# OpenProg-18F2550-2.net
KiCad netlist of a schematic drawn in EAGLE
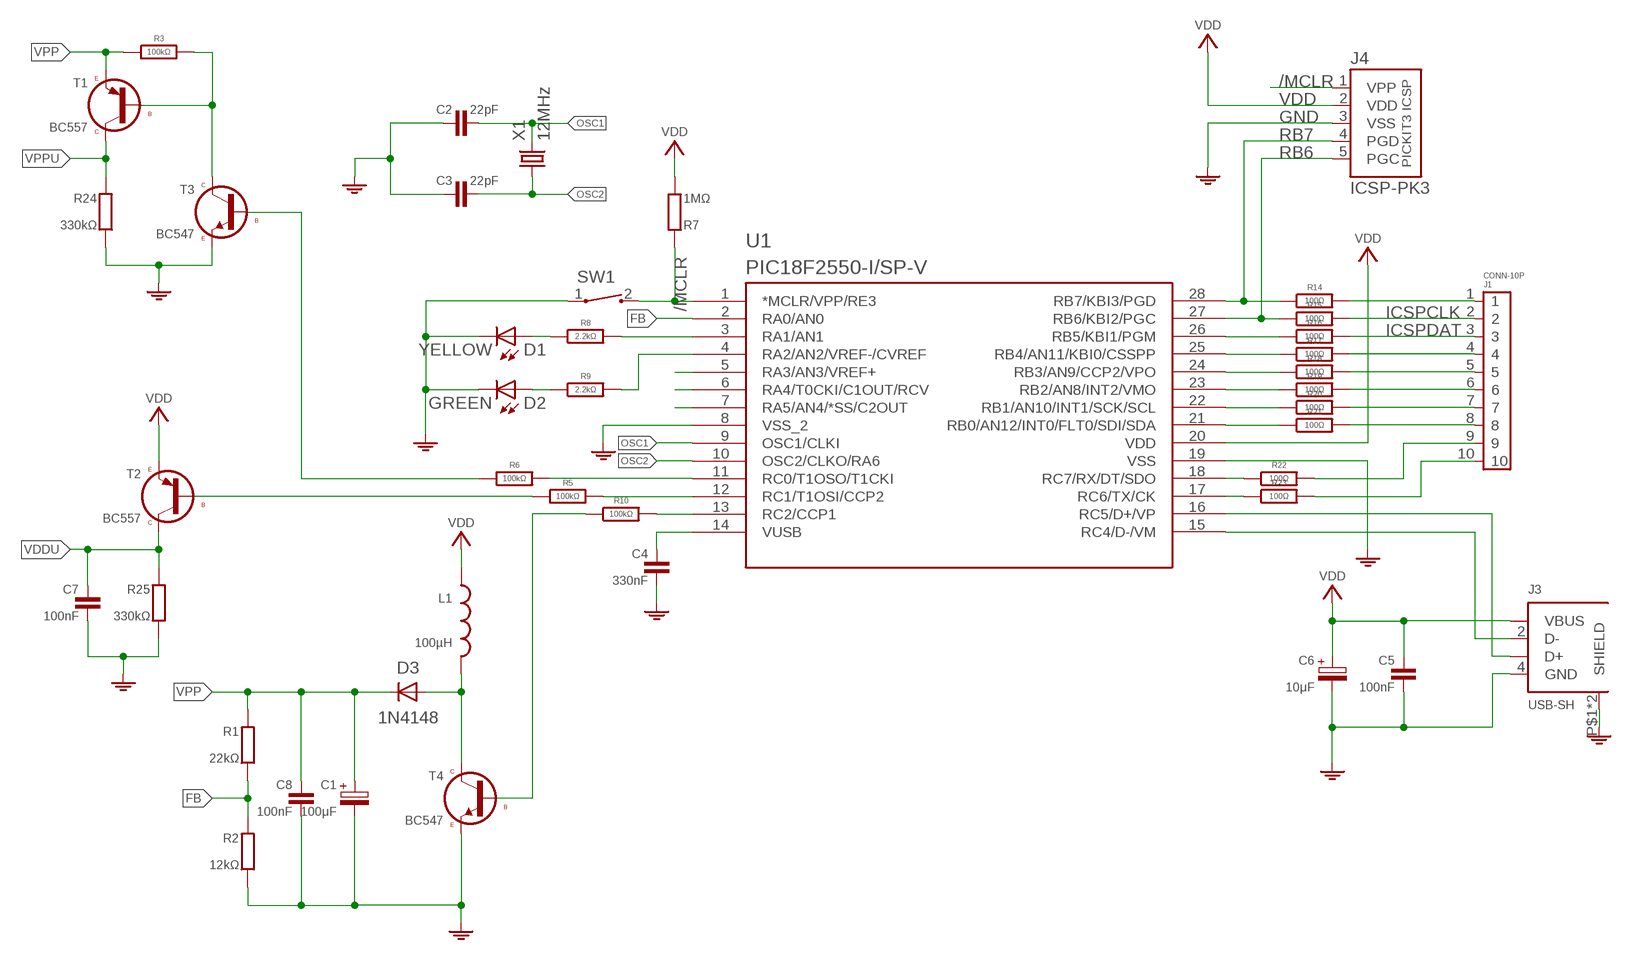
[diagram p0: schematic, sheet 1]

(export (version "E")
  (design (tool "Eeschema 10.0.6"))
  (components
    (comp (ref "C1")
      (value "100μF")
      (footprint "eagle-import:E5-5")
      (libsource (lib "eagle-import") (part "CPOLE5-5"))
    )
    (comp (ref "C2")
      (value "22pF")
      (footprint "eagle-import:C025-015X024")
      (libsource (lib "eagle-import") (part "C-H025-015X024"))
    )
    (comp (ref "C3")
      (value "22pF")
      (footprint "eagle-import:C025-015X024")
      (libsource (lib "eagle-import") (part "C-H025-015X024"))
    )
    (comp (ref "C4")
      (value "330nF")
      (footprint "eagle-import:C050-030X075")
      (libsource (lib "eagle-import") (part "C050-030X075"))
    )
    (comp (ref "C5")
      (value "100nF")
      (footprint "eagle-import:C050-025X075")
      (libsource (lib "eagle-import") (part "C050-025X075"))
    )
    (comp (ref "C6")
      (value "10μF")
      (footprint "eagle-import:E5-5")
      (libsource (lib "eagle-import") (part "CPOLE5-5"))
    )
    (comp (ref "C7")
      (value "100nF")
      (footprint "eagle-import:C050-025X075")
      (libsource (lib "eagle-import") (part "C050-025X075"))
    )
    (comp (ref "C8")
      (value "100nF")
      (footprint "eagle-import:C050-025X075")
      (libsource (lib "eagle-import") (part "C050-025X075"))
    )
    (comp (ref "D1")
      (value "YELLOW")
      (footprint "eagle-import:LED3MM")
      (libsource (lib "eagle-import") (part "LED-H-3MM"))
    )
    (comp (ref "D2")
      (value "GREEN")
      (footprint "eagle-import:LED3MM")
      (libsource (lib "eagle-import") (part "LED-H-3MM"))
    )
    (comp (ref "D3")
      (value "1N4148")
      (footprint "eagle-import:DO34-7")
      (libsource (lib "eagle-import") (part "1N4148-HDO34-7"))
    )
    (comp (ref "J1")
      (value "CONN-10P")
      (footprint "eagle-import:CONN-10P")
      (libsource (lib "eagle-import") (part "CONN-10P"))
    )
    (comp (ref "J3")
      (value "USB-SH")
      (footprint "eagle-import:USB-B-PRINT")
      (libsource (lib "eagle-import") (part "USB-SH"))
    )
    (comp (ref "J4")
      (value "ICSP-PK3")
      (footprint "eagle-import:PIC-PK3")
      (libsource (lib "eagle-import") (part "PICKIT3-ICSP-PK3"))
    )
    (comp (ref "L1")
      (value "100µH")
      (footprint "eagle-import:L-03_10V")
      (libsource (lib "eagle-import") (part "L02/10"))
    )
    (comp (ref "R1")
      (value "22kΩ")
      (footprint "eagle-import:0204_10-V")
      (libsource (lib "eagle-import") (part "R0204/10-V"))
    )
    (comp (ref "R2")
      (value "12kΩ")
      (footprint "eagle-import:0204_10-V")
      (libsource (lib "eagle-import") (part "R0204/10-V"))
    )
    (comp (ref "R3")
      (value "100kΩ")
      (footprint "eagle-import:0204_10-V")
      (libsource (lib "eagle-import") (part "R-H0204/10-V"))
    )
    (comp (ref "R5")
      (value "100kΩ")
      (footprint "eagle-import:0204_10")
      (libsource (lib "eagle-import") (part "R-H0204/10"))
    )
    (comp (ref "R6")
      (value "100kΩ")
      (footprint "eagle-import:0204_10")
      (libsource (lib "eagle-import") (part "R-H0204/10"))
    )
    (comp (ref "R7")
      (value "1MΩ")
      (footprint "eagle-import:0204_10-V")
      (libsource (lib "eagle-import") (part "R0204/10-V"))
    )
    (comp (ref "R8")
      (value "2.2kΩ")
      (footprint "eagle-import:0204_10")
      (libsource (lib "eagle-import") (part "R-H0204/10"))
    )
    (comp (ref "R9")
      (value "2.2kΩ")
      (footprint "eagle-import:0204_10")
      (libsource (lib "eagle-import") (part "R-H0204/10"))
    )
    (comp (ref "R10")
      (value "100kΩ")
      (footprint "eagle-import:0204_10")
      (libsource (lib "eagle-import") (part "R-H0204/10"))
    )
    (comp (ref "R14")
      (value "100Ω")
      (footprint "eagle-import:0204_10")
      (libsource (lib "eagle-import") (part "R-H0204/10"))
    )
    (comp (ref "R15")
      (value "100Ω")
      (footprint "eagle-import:0204_10")
      (libsource (lib "eagle-import") (part "R-H0204/10"))
    )
    (comp (ref "R16")
      (value "100Ω")
      (footprint "eagle-import:0204_10")
      (libsource (lib "eagle-import") (part "R-H0204/10"))
    )
    (comp (ref "R17")
      (value "100Ω")
      (footprint "eagle-import:0204_10")
      (libsource (lib "eagle-import") (part "R-H0204/10"))
    )
    (comp (ref "R18")
      (value "100Ω")
      (footprint "eagle-import:0204_10")
      (libsource (lib "eagle-import") (part "R-H0204/10"))
    )
    (comp (ref "R19")
      (value "100Ω")
      (footprint "eagle-import:0204_10")
      (libsource (lib "eagle-import") (part "R-H0204/10"))
    )
    (comp (ref "R20")
      (value "100Ω")
      (footprint "eagle-import:0204_10")
      (libsource (lib "eagle-import") (part "R-H0204/10"))
    )
    (comp (ref "R21")
      (value "100Ω")
      (footprint "eagle-import:0204_10")
      (libsource (lib "eagle-import") (part "R-H0204/10"))
    )
    (comp (ref "R22")
      (value "100Ω")
      (footprint "eagle-import:0204_10")
      (libsource (lib "eagle-import") (part "R-H0204/10"))
    )
    (comp (ref "R23")
      (value "100Ω")
      (footprint "eagle-import:0204_10")
      (libsource (lib "eagle-import") (part "R-H0204/10"))
    )
    (comp (ref "R24")
      (value "330kΩ")
      (footprint "eagle-import:0204_10-V")
      (libsource (lib "eagle-import") (part "R0204/10-V"))
    )
    (comp (ref "R25")
      (value "330kΩ")
      (footprint "eagle-import:0204_10-V")
      (libsource (lib "eagle-import") (part "R0204/10-V"))
    )
    (comp (ref "SW1")
      (value "PUSHBUTTON-P1T")
      (footprint "eagle-import:PB-1P1T")
      (libsource (lib "eagle-import") (part "PUSHBUTTON-P1T"))
    )
    (comp (ref "T1")
      (value "BC557")
      (footprint "eagle-import:TO92-CBE-A")
      (libsource (lib "eagle-import") (part "BC557CBE-A"))
    )
    (comp (ref "T2")
      (value "BC557")
      (footprint "eagle-import:TO92-CBE-A")
      (libsource (lib "eagle-import") (part "BC557CBE-A"))
    )
    (comp (ref "T3")
      (value "BC547")
      (footprint "eagle-import:TO92-CBE-A")
      (libsource (lib "eagle-import") (part "BC547-A"))
    )
    (comp (ref "T4")
      (value "BC547")
      (footprint "eagle-import:TO92-CBE-A")
      (libsource (lib "eagle-import") (part "BC547-A"))
    )
    (comp (ref "U1")
      (value "PIC18F2550-I/SP-V")
      (footprint "eagle-import:DIL28-3_V")
      (libsource (lib "eagle-import") (part "PIC18F2550-I/SP-V"))
    )
    (comp (ref "X1")
      (value "12MHz")
      (footprint "eagle-import:HC49")
      (libsource (lib "eagle-import") (part "CRYSTALHC49"))
    )
  )
  (nets
    (net (code "1") (name "/ICSPCLK") (class "Default")
      (node (ref "J1") (pin "2") (pinfunction "2_2") (pintype "passive"))
      (node (ref "R15") (pin "2") (pinfunction "2_2") (pintype "passive"))
    )
    (net (code "2") (name "/ICSPDAT") (class "Default")
      (node (ref "J1") (pin "3") (pinfunction "3_3") (pintype "passive"))
      (node (ref "R16") (pin "2") (pinfunction "2_2") (pintype "passive"))
    )
    (net (code "3") (name "/RB6") (class "Default")
      (node (ref "J4") (pin "5") (pinfunction "PGC_5") (pintype "passive"))
      (node (ref "R15") (pin "1") (pinfunction "1_1") (pintype "passive"))
      (node (ref "U1") (pin "27") (pinfunction "RB6/KBI2/PGC_27") (pintype "passive"))
    )
    (net (code "4") (name "/RB7") (class "Default")
      (node (ref "J4") (pin "4") (pinfunction "PGD_4") (pintype "passive"))
      (node (ref "R14") (pin "1") (pinfunction "1_1") (pintype "passive"))
      (node (ref "U1") (pin "28") (pinfunction "RB7/KBI3/PGD_28") (pintype "passive"))
    )
    (net (code "5") (name "/{slash}MCLR") (class "Default")
      (node (ref "J4") (pin "1") (pinfunction "VPP_1") (pintype "passive"))
      (node (ref "R7") (pin "1") (pinfunction "2_1") (pintype "passive"))
      (node (ref "SW1") (pin "2") (pinfunction "2_2") (pintype "passive"))
      (node (ref "U1") (pin "1") (pinfunction "*MCLR/VPP/RE3_1") (pintype "passive"))
    )
    (net (code "6") (name "FB") (class "Default")
      (node (ref "R1") (pin "2") (pinfunction "1_2") (pintype "passive"))
      (node (ref "R2") (pin "1") (pinfunction "2_1") (pintype "passive"))
      (node (ref "U1") (pin "2") (pinfunction "RA0/AN0_2") (pintype "passive"))
    )
    (net (code "7") (name "GND") (class "Default")
      (node (ref "C1") (pin "-") (pinfunction "-_-") (pintype "passive"))
      (node (ref "C2") (pin "1") (pinfunction "1_1") (pintype "passive"))
      (node (ref "C3") (pin "1") (pinfunction "1_1") (pintype "passive"))
      (node (ref "C4") (pin "2") (pinfunction "2_2") (pintype "passive"))
      (node (ref "C5") (pin "2") (pinfunction "2_2") (pintype "passive"))
      (node (ref "C6") (pin "-") (pinfunction "-_-") (pintype "passive"))
      (node (ref "C7") (pin "2") (pinfunction "2_2") (pintype "passive"))
      (node (ref "C8") (pin "2") (pinfunction "2_2") (pintype "passive"))
      (node (ref "D1") (pin "K") (pinfunction "C_K") (pintype "passive"))
      (node (ref "D2") (pin "K") (pinfunction "C_K") (pintype "passive"))
      (node (ref "J3") (pin "4") (pinfunction "GND_4") (pintype "bidirectional"))
      (node (ref "J3") (pin "P$1") (pinfunction "SHIELD_P$1") (pintype "bidirectional"))
      (node (ref "J3") (pin "P$2") (pinfunction "SHIELD_P$2") (pintype "bidirectional"))
      (node (ref "J4") (pin "3") (pinfunction "VSS_3") (pintype "passive"))
      (node (ref "R2") (pin "2") (pinfunction "1_2") (pintype "passive"))
      (node (ref "R24") (pin "2") (pinfunction "1_2") (pintype "passive"))
      (node (ref "R25") (pin "2") (pinfunction "1_2") (pintype "passive"))
      (node (ref "SW1") (pin "1") (pinfunction "1_1") (pintype "passive"))
      (node (ref "T3") (pin "3") (pinfunction "E_3") (pintype "passive"))
      (node (ref "T4") (pin "3") (pinfunction "E_3") (pintype "passive"))
      (node (ref "U1") (pin "19") (pinfunction "VSS_19") (pintype "passive"))
      (node (ref "U1") (pin "8") (pinfunction "VSS_2_8") (pintype "passive"))
    )
    (net (code "8") (name "Net-(D1-PadA)") (class "Default")
      (node (ref "D1") (pin "A") (pinfunction "A_A") (pintype "passive"))
      (node (ref "R8") (pin "1") (pinfunction "1_1") (pintype "passive"))
    )
    (net (code "9") (name "Net-(D2-PadA)") (class "Default")
      (node (ref "D2") (pin "A") (pinfunction "A_A") (pintype "passive"))
      (node (ref "R9") (pin "1") (pinfunction "1_1") (pintype "passive"))
    )
    (net (code "10") (name "Net-(J1-Pad1)") (class "Default")
      (node (ref "J1") (pin "1") (pinfunction "1_1") (pintype "passive"))
      (node (ref "R14") (pin "2") (pinfunction "2_2") (pintype "passive"))
    )
    (net (code "11") (name "Net-(J1-Pad4)") (class "Default")
      (node (ref "J1") (pin "4") (pinfunction "4_4") (pintype "passive"))
      (node (ref "R17") (pin "2") (pinfunction "2_2") (pintype "passive"))
    )
    (net (code "12") (name "Net-(J1-Pad5)") (class "Default")
      (node (ref "J1") (pin "5") (pinfunction "5_5") (pintype "passive"))
      (node (ref "R18") (pin "2") (pinfunction "2_2") (pintype "passive"))
    )
    (net (code "13") (name "Net-(J1-Pad6)") (class "Default")
      (node (ref "J1") (pin "6") (pinfunction "6_6") (pintype "passive"))
      (node (ref "R19") (pin "2") (pinfunction "2_2") (pintype "passive"))
    )
    (net (code "14") (name "Net-(J1-Pad7)") (class "Default")
      (node (ref "J1") (pin "7") (pinfunction "7_7") (pintype "passive"))
      (node (ref "R20") (pin "2") (pinfunction "2_2") (pintype "passive"))
    )
    (net (code "15") (name "Net-(J1-Pad8)") (class "Default")
      (node (ref "J1") (pin "8") (pinfunction "8_8") (pintype "passive"))
      (node (ref "R21") (pin "2") (pinfunction "2_2") (pintype "passive"))
    )
    (net (code "16") (name "Net-(J1-Pad9)") (class "Default")
      (node (ref "J1") (pin "9") (pinfunction "9_9") (pintype "passive"))
      (node (ref "R22") (pin "2") (pinfunction "2_2") (pintype "passive"))
    )
    (net (code "17") (name "Net-(J1-Pad10)") (class "Default")
      (node (ref "J1") (pin "10") (pinfunction "10_10") (pintype "passive"))
      (node (ref "R23") (pin "2") (pinfunction "2_2") (pintype "passive"))
    )
    (net (code "18") (name "Net-(J3-D+)") (class "Default")
      (node (ref "J3") (pin "3") (pinfunction "D+_3") (pintype "bidirectional"))
      (node (ref "U1") (pin "16") (pinfunction "RC5/D+/VP_16") (pintype "passive"))
    )
    (net (code "19") (name "Net-(J3-D-)") (class "Default")
      (node (ref "J3") (pin "2") (pinfunction "D-_2") (pintype "bidirectional"))
      (node (ref "U1") (pin "15") (pinfunction "RC4/D-/VM_15") (pintype "passive"))
    )
    (net (code "20") (name "Net-(T1-B)") (class "Default")
      (node (ref "R3") (pin "2") (pinfunction "2_2") (pintype "passive"))
      (node (ref "T1") (pin "2") (pinfunction "B_2") (pintype "passive"))
      (node (ref "T3") (pin "1") (pinfunction "C_1") (pintype "passive"))
    )
    (net (code "21") (name "Net-(T2-B)") (class "Default")
      (node (ref "R5") (pin "1") (pinfunction "1_1") (pintype "passive"))
      (node (ref "T2") (pin "2") (pinfunction "B_2") (pintype "passive"))
    )
    (net (code "22") (name "Net-(T3-B)") (class "Default")
      (node (ref "R6") (pin "1") (pinfunction "1_1") (pintype "passive"))
      (node (ref "T3") (pin "2") (pinfunction "B_2") (pintype "passive"))
    )
    (net (code "23") (name "Net-(T4-B)") (class "Default")
      (node (ref "R10") (pin "1") (pinfunction "1_1") (pintype "passive"))
      (node (ref "T4") (pin "2") (pinfunction "B_2") (pintype "passive"))
    )
    (net (code "24") (name "Net-(T4-C)") (class "Default")
      (node (ref "D3") (pin "A") (pinfunction "A_A") (pintype "passive"))
      (node (ref "L1") (pin "2") (pinfunction "2_2") (pintype "passive"))
      (node (ref "T4") (pin "1") (pinfunction "C_1") (pintype "passive"))
    )
    (net (code "25") (name "Net-(U1-RA1{slash}AN1)") (class "Default")
      (node (ref "R8") (pin "2") (pinfunction "2_2") (pintype "passive"))
      (node (ref "U1") (pin "3") (pinfunction "RA1/AN1_3") (pintype "passive"))
    )
    (net (code "26") (name "Net-(U1-RA2{slash}AN2{slash}VREF-{slash}CVREF)") (class "Default")
      (node (ref "R9") (pin "2") (pinfunction "2_2") (pintype "passive"))
      (node (ref "U1") (pin "4") (pinfunction "RA2/AN2/VREF-/CVREF_4") (pintype "passive"))
    )
    (net (code "27") (name "Net-(U1-RB0{slash}AN12{slash}INT0{slash}FLT0{slash}SDI{slash}SDA)") (class "Default")
      (node (ref "R21") (pin "1") (pinfunction "1_1") (pintype "passive"))
      (node (ref "U1") (pin "21") (pinfunction "RB0/AN12/INT0/FLT0/SDI/SDA_21") (pintype "passive"))
    )
    (net (code "28") (name "Net-(U1-RB1{slash}AN10{slash}INT1{slash}SCK{slash}SCL)") (class "Default")
      (node (ref "R20") (pin "1") (pinfunction "1_1") (pintype "passive"))
      (node (ref "U1") (pin "22") (pinfunction "RB1/AN10/INT1/SCK/SCL_22") (pintype "passive"))
    )
    (net (code "29") (name "Net-(U1-RB2{slash}AN8{slash}INT2{slash}VMO)") (class "Default")
      (node (ref "R19") (pin "1") (pinfunction "1_1") (pintype "passive"))
      (node (ref "U1") (pin "23") (pinfunction "RB2/AN8/INT2/VMO_23") (pintype "passive"))
    )
    (net (code "30") (name "Net-(U1-RB3{slash}AN9{slash}CCP2{slash}VPO)") (class "Default")
      (node (ref "R18") (pin "1") (pinfunction "1_1") (pintype "passive"))
      (node (ref "U1") (pin "24") (pinfunction "RB3/AN9/CCP2/VPO_24") (pintype "passive"))
    )
    (net (code "31") (name "Net-(U1-RB4{slash}AN11{slash}KBI0{slash}CSSPP)") (class "Default")
      (node (ref "R17") (pin "1") (pinfunction "1_1") (pintype "passive"))
      (node (ref "U1") (pin "25") (pinfunction "RB4/AN11/KBI0/CSSPP_25") (pintype "passive"))
    )
    (net (code "32") (name "Net-(U1-RB5{slash}KBI1{slash}PGM)") (class "Default")
      (node (ref "R16") (pin "1") (pinfunction "1_1") (pintype "passive"))
      (node (ref "U1") (pin "26") (pinfunction "RB5/KBI1/PGM_26") (pintype "passive"))
    )
    (net (code "33") (name "Net-(U1-RC0{slash}T1OSO{slash}T1CKI)") (class "Default")
      (node (ref "R6") (pin "2") (pinfunction "2_2") (pintype "passive"))
      (node (ref "U1") (pin "11") (pinfunction "RC0/T1OSO/T1CKI_11") (pintype "passive"))
    )
    (net (code "34") (name "Net-(U1-RC1{slash}T1OSI{slash}CCP2)") (class "Default")
      (node (ref "R5") (pin "2") (pinfunction "2_2") (pintype "passive"))
      (node (ref "U1") (pin "12") (pinfunction "RC1/T1OSI/CCP2_12") (pintype "passive"))
    )
    (net (code "35") (name "Net-(U1-RC2{slash}CCP1)") (class "Default")
      (node (ref "R10") (pin "2") (pinfunction "2_2") (pintype "passive"))
      (node (ref "U1") (pin "13") (pinfunction "RC2/CCP1_13") (pintype "passive"))
    )
    (net (code "36") (name "Net-(U1-RC6{slash}TX{slash}CK)") (class "Default")
      (node (ref "R23") (pin "1") (pinfunction "1_1") (pintype "passive"))
      (node (ref "U1") (pin "17") (pinfunction "RC6/TX/CK_17") (pintype "passive"))
    )
    (net (code "37") (name "Net-(U1-RC7{slash}RX{slash}DT{slash}SDO)") (class "Default")
      (node (ref "R22") (pin "1") (pinfunction "1_1") (pintype "passive"))
      (node (ref "U1") (pin "18") (pinfunction "RC7/RX/DT/SDO_18") (pintype "passive"))
    )
    (net (code "38") (name "Net-(U1-VUSB)") (class "Default")
      (node (ref "C4") (pin "1") (pinfunction "1_1") (pintype "passive"))
      (node (ref "U1") (pin "14") (pinfunction "VUSB_14") (pintype "passive"))
    )
    (net (code "39") (name "OSC1") (class "Default")
      (node (ref "C2") (pin "2") (pinfunction "2_2") (pintype "passive"))
      (node (ref "U1") (pin "9") (pinfunction "OSC1/CLKI_9") (pintype "passive"))
      (node (ref "X1") (pin "2") (pinfunction "2_2") (pintype "passive"))
    )
    (net (code "40") (name "OSC2") (class "Default")
      (node (ref "C3") (pin "2") (pinfunction "2_2") (pintype "passive"))
      (node (ref "U1") (pin "10") (pinfunction "OSC2/CLKO/RA6_10") (pintype "passive"))
      (node (ref "X1") (pin "1") (pinfunction "1_1") (pintype "passive"))
    )
    (net (code "41") (name "VDD") (class "Default")
      (node (ref "C5") (pin "1") (pinfunction "1_1") (pintype "passive"))
      (node (ref "C6") (pin "+") (pinfunction "+_+") (pintype "passive"))
      (node (ref "J3") (pin "1") (pinfunction "VBUS_1") (pintype "bidirectional"))
      (node (ref "J4") (pin "2") (pinfunction "VDD_2") (pintype "passive"))
      (node (ref "L1") (pin "1") (pinfunction "1_1") (pintype "passive"))
      (node (ref "R7") (pin "2") (pinfunction "1_2") (pintype "passive"))
      (node (ref "T2") (pin "3") (pinfunction "E_3") (pintype "passive"))
      (node (ref "U1") (pin "20") (pinfunction "VDD_20") (pintype "passive"))
    )
    (net (code "42") (name "VDDU") (class "Default")
      (node (ref "C7") (pin "1") (pinfunction "1_1") (pintype "passive"))
      (node (ref "R25") (pin "1") (pinfunction "2_1") (pintype "passive"))
      (node (ref "T2") (pin "1") (pinfunction "C_1") (pintype "passive"))
    )
    (net (code "43") (name "VPP") (class "Default")
      (node (ref "C1") (pin "+") (pinfunction "+_+") (pintype "passive"))
      (node (ref "C8") (pin "1") (pinfunction "1_1") (pintype "passive"))
      (node (ref "D3") (pin "C") (pinfunction "C_C") (pintype "passive"))
      (node (ref "R1") (pin "1") (pinfunction "2_1") (pintype "passive"))
      (node (ref "R3") (pin "1") (pinfunction "1_1") (pintype "passive"))
      (node (ref "T1") (pin "3") (pinfunction "E_3") (pintype "passive"))
    )
    (net (code "44") (name "VPPU") (class "Default")
      (node (ref "R24") (pin "1") (pinfunction "2_1") (pintype "passive"))
      (node (ref "T1") (pin "1") (pinfunction "C_1") (pintype "passive"))
    )
    (net (code "45") (name "unconnected-(U1-RA3{slash}AN3{slash}VREF+-Pad5)") (class "Default")
      (node (ref "U1") (pin "5") (pinfunction "RA3/AN3/VREF+_5") (pintype "passive"))
    )
    (net (code "46") (name "unconnected-(U1-RA4{slash}T0CKI{slash}C1OUT{slash}RCV-Pad6)") (class "Default")
      (node (ref "U1") (pin "6") (pinfunction "RA4/T0CKI/C1OUT/RCV_6") (pintype "passive"))
    )
    (net (code "47") (name "unconnected-(U1-RA5{slash}AN4{slash}*SS{slash}C2OUT-Pad7)") (class "Default")
      (node (ref "U1") (pin "7") (pinfunction "RA5/AN4/*SS/C2OUT_7") (pintype "passive"))
    )
  )
)
